# 03_USART.net
KiCad netlist of a schematic drawn in Altium Designer
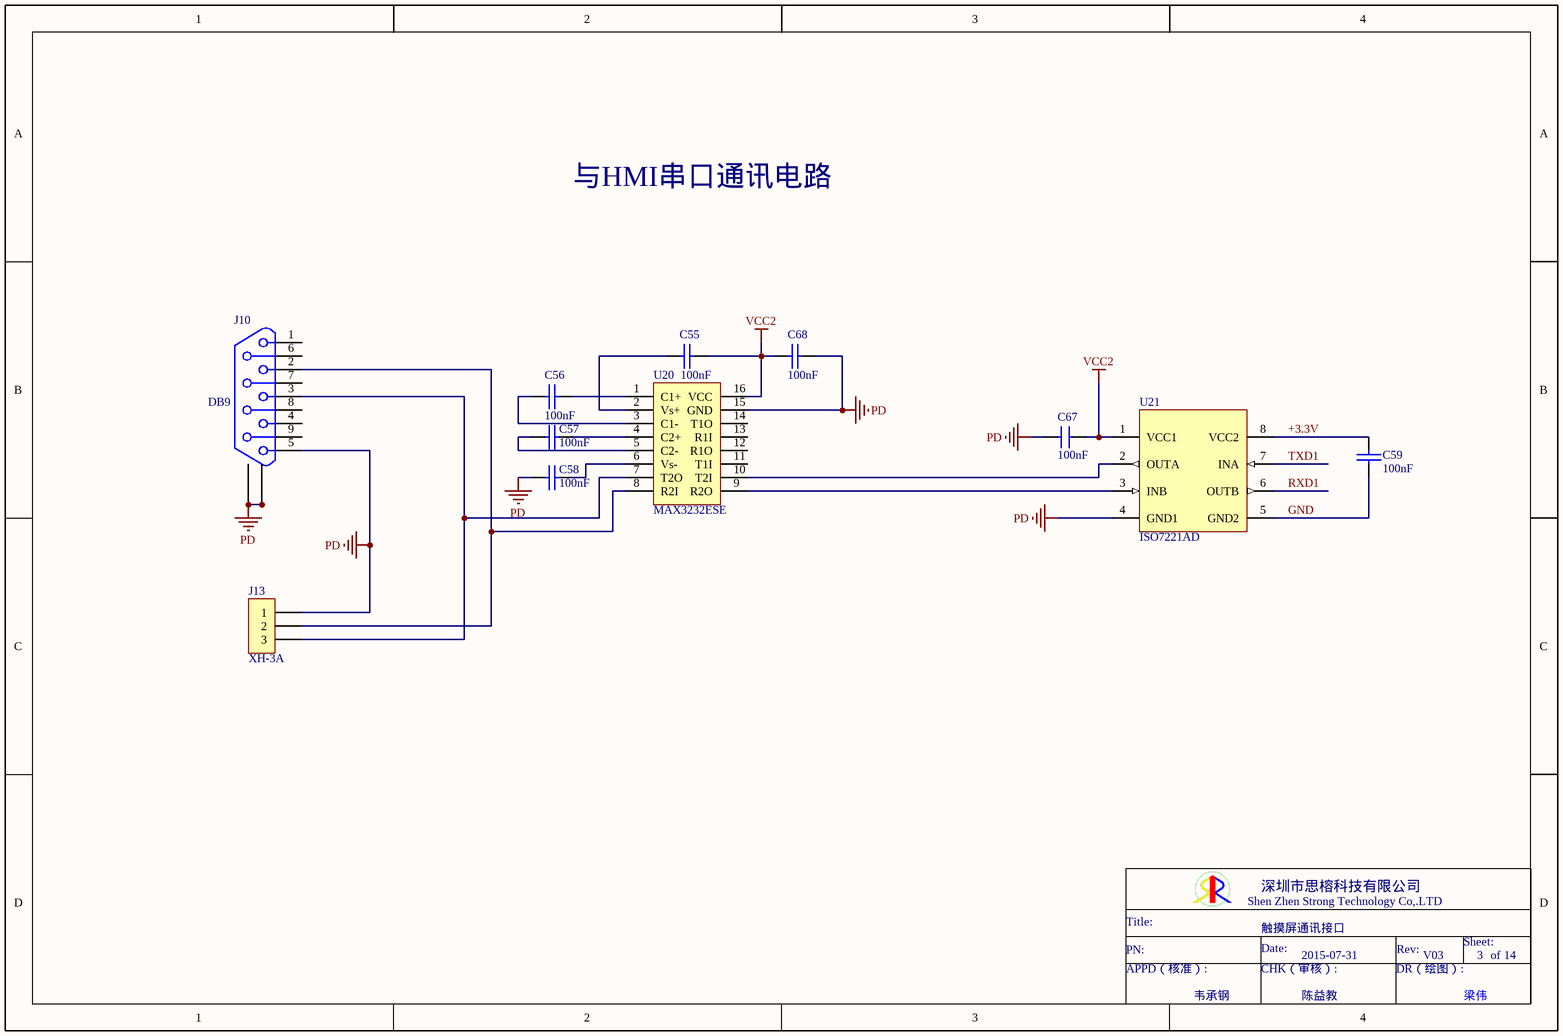
[diagram p0: 03_USART.SchDoc]

(export (version "E")
  (design (tool "Eeschema 10.0.6"))
  (components
    (comp (ref "C55") (value "100nF") (footprint "0603C") (libsource (lib "WeiCHGSCH") (part "CAP")))
    (comp (ref "C56") (value "100nF") (footprint "0603C") (libsource (lib "WeiCHGSCH") (part "CAP")))
    (comp (ref "C57") (value "100nF") (footprint "0603C") (libsource (lib "WeiCHGSCH") (part "CAP")))
    (comp (ref "C58") (value "100nF") (footprint "0603C") (libsource (lib "WeiCHGSCH") (part "CAP")))
    (comp (ref "C59") (value "100nF") (footprint "0603C") (libsource (lib "WeiCHGSCH") (part "CAP")))
    (comp (ref "C67")
      (value "100nF")
      (footprint "0603C")
      (description "Capacitor")
      (libsource (lib "*") (part "电容"))
    )
    (comp (ref "C68") (value "100nF") (footprint "0603C") (libsource (lib "WeiCHGSCH") (part "CAP")))
    (comp (ref "J10") (value "DB9") (footprint "DSUB1.385") (libsource (lib "WeiCHGSCH") (part "DB9")))
    (comp (ref "J13") (value "XH-3A") (footprint "CN3-2.54") (libsource (lib "Mylibrary") (part "CON3")))
    (comp (ref "U20") (value "MAX3232ESE") (footprint "SO-16") (libsource (lib "WeiCHGSCH") (part "MAX232")))
    (comp (ref "U21")
      (value "ISO7221AD")
      (footprint "SOP8")
      (libsource (lib "ISO7221xD") (part "Component_1"))
    )
  )
  (nets
    (net (code "1") (name "/+3.3V") (class "Default")
      (node (ref "C59") (pin "2") (pinfunction "2_2") (pintype "passive"))
      (node (ref "U21") (pin "8") (pinfunction "VCC2_8") (pintype "passive"))
    )
    (net (code "2") (name "/GND") (class "Default")
      (node (ref "C59") (pin "1") (pinfunction "1_1") (pintype "passive"))
      (node (ref "U21") (pin "5") (pinfunction "GND2_5") (pintype "passive"))
    )
    (net (code "3") (name "/RXD1") (class "Default")
      (node (ref "U21") (pin "6") (pinfunction "OUTB_6") (pintype "output"))
    )
    (net (code "4") (name "/TXD1") (class "Default")
      (node (ref "U21") (pin "7") (pinfunction "INA_7") (pintype "input"))
    )
    (net (code "5") (name "Net-(U20-C1+)") (class "Default")
      (node (ref "C56") (pin "1") (pinfunction "1_1") (pintype "passive"))
      (node (ref "U20") (pin "1") (pinfunction "C1+_1") (pintype "passive"))
    )
    (net (code "6") (name "Net-(U20-C1-)") (class "Default")
      (node (ref "C56") (pin "2") (pinfunction "2_2") (pintype "passive"))
      (node (ref "U20") (pin "3") (pinfunction "C1-_3") (pintype "passive"))
    )
    (net (code "7") (name "Net-(U20-C2+)") (class "Default")
      (node (ref "C57") (pin "2") (pinfunction "2_2") (pintype "passive"))
      (node (ref "U20") (pin "4") (pinfunction "C2+_4") (pintype "passive"))
    )
    (net (code "8") (name "Net-(U20-C2-)") (class "Default")
      (node (ref "C57") (pin "1") (pinfunction "1_1") (pintype "passive"))
      (node (ref "U20") (pin "5") (pinfunction "C2-_5") (pintype "passive"))
    )
    (net (code "9") (name "Net-(U20-R2I)") (class "Default")
      (node (ref "J10") (pin "2") (pinfunction "2_2") (pintype "passive"))
      (node (ref "J13") (pin "2") (pinfunction "2_2") (pintype "passive"))
      (node (ref "U20") (pin "8") (pinfunction "R2I_8") (pintype "passive"))
    )
    (net (code "10") (name "Net-(U20-R2O)") (class "Default")
      (node (ref "U20") (pin "9") (pinfunction "R2O_9") (pintype "passive"))
      (node (ref "U21") (pin "3") (pinfunction "INB_3") (pintype "input"))
    )
    (net (code "11") (name "Net-(U20-T2I)") (class "Default")
      (node (ref "U20") (pin "10") (pinfunction "T2I_10") (pintype "passive"))
      (node (ref "U21") (pin "2") (pinfunction "OUTA_2") (pintype "output"))
    )
    (net (code "12") (name "Net-(U20-T2O)") (class "Default")
      (node (ref "J10") (pin "3") (pinfunction "3_3") (pintype "passive"))
      (node (ref "J13") (pin "3") (pinfunction "3_3") (pintype "passive"))
      (node (ref "U20") (pin "7") (pinfunction "T2O_7") (pintype "passive"))
    )
    (net (code "13") (name "Net-(U20-Vs+)") (class "Default")
      (node (ref "C55") (pin "1") (pinfunction "1_1") (pintype "passive"))
      (node (ref "U20") (pin "2") (pinfunction "Vs+_2") (pintype "passive"))
    )
    (net (code "14") (name "Net-(U20-Vs-)") (class "Default")
      (node (ref "C58") (pin "2") (pinfunction "2_2") (pintype "passive"))
      (node (ref "U20") (pin "6") (pinfunction "Vs-_6") (pintype "passive"))
    )
    (net (code "15") (name "PD") (class "Default")
      (node (ref "C58") (pin "1") (pinfunction "1_1") (pintype "passive"))
      (node (ref "C67") (pin "1") (pinfunction "1_1") (pintype "passive"))
      (node (ref "C68") (pin "1") (pinfunction "1_1") (pintype "passive"))
      (node (ref "J10") (pin "10") (pinfunction "10_10") (pintype "passive"))
      (node (ref "J10") (pin "11") (pinfunction "11_11") (pintype "passive"))
      (node (ref "J10") (pin "5") (pinfunction "5_5") (pintype "passive"))
      (node (ref "J13") (pin "1") (pinfunction "1_1") (pintype "passive"))
      (node (ref "U20") (pin "15") (pinfunction "GND_15") (pintype "passive"))
      (node (ref "U21") (pin "4") (pinfunction "GND1_4") (pintype "passive"))
    )
    (net (code "16") (name "VCC2") (class "Default")
      (node (ref "C55") (pin "2") (pinfunction "2_2") (pintype "passive"))
      (node (ref "C67") (pin "2") (pinfunction "2_2") (pintype "passive"))
      (node (ref "C68") (pin "2") (pinfunction "2_2") (pintype "passive"))
      (node (ref "U20") (pin "16") (pinfunction "VCC_16") (pintype "passive"))
      (node (ref "U21") (pin "1") (pinfunction "VCC1_1") (pintype "passive"))
    )
    (net (code "17") (name "unconnected-(J10-Pad1)") (class "Default")
      (node (ref "J10") (pin "1") (pinfunction "1_1") (pintype "passive"))
    )
    (net (code "18") (name "unconnected-(J10-Pad4)") (class "Default")
      (node (ref "J10") (pin "4") (pinfunction "4_4") (pintype "passive"))
    )
    (net (code "19") (name "unconnected-(J10-Pad6)") (class "Default")
      (node (ref "J10") (pin "6") (pinfunction "6_6") (pintype "passive"))
    )
    (net (code "20") (name "unconnected-(J10-Pad7)") (class "Default")
      (node (ref "J10") (pin "7") (pinfunction "7_7") (pintype "passive"))
    )
    (net (code "21") (name "unconnected-(J10-Pad8)") (class "Default")
      (node (ref "J10") (pin "8") (pinfunction "8_8") (pintype "passive"))
    )
    (net (code "22") (name "unconnected-(J10-Pad9)") (class "Default")
      (node (ref "J10") (pin "9") (pinfunction "9_9") (pintype "passive"))
    )
    (net (code "23") (name "unconnected-(U20-R1I-Pad13)") (class "Default")
      (node (ref "U20") (pin "13") (pinfunction "R1I_13") (pintype "passive"))
    )
    (net (code "24") (name "unconnected-(U20-R1O-Pad12)") (class "Default")
      (node (ref "U20") (pin "12") (pinfunction "R1O_12") (pintype "passive"))
    )
    (net (code "25") (name "unconnected-(U20-T1I-Pad11)") (class "Default")
      (node (ref "U20") (pin "11") (pinfunction "T1I_11") (pintype "passive"))
    )
    (net (code "26") (name "unconnected-(U20-T1O-Pad14)") (class "Default")
      (node (ref "U20") (pin "14") (pinfunction "T1O_14") (pintype "passive"))
    )
  )
)
